# PowerManagementMysensors2.net
KiCad netlist of a schematic drawn in EAGLE
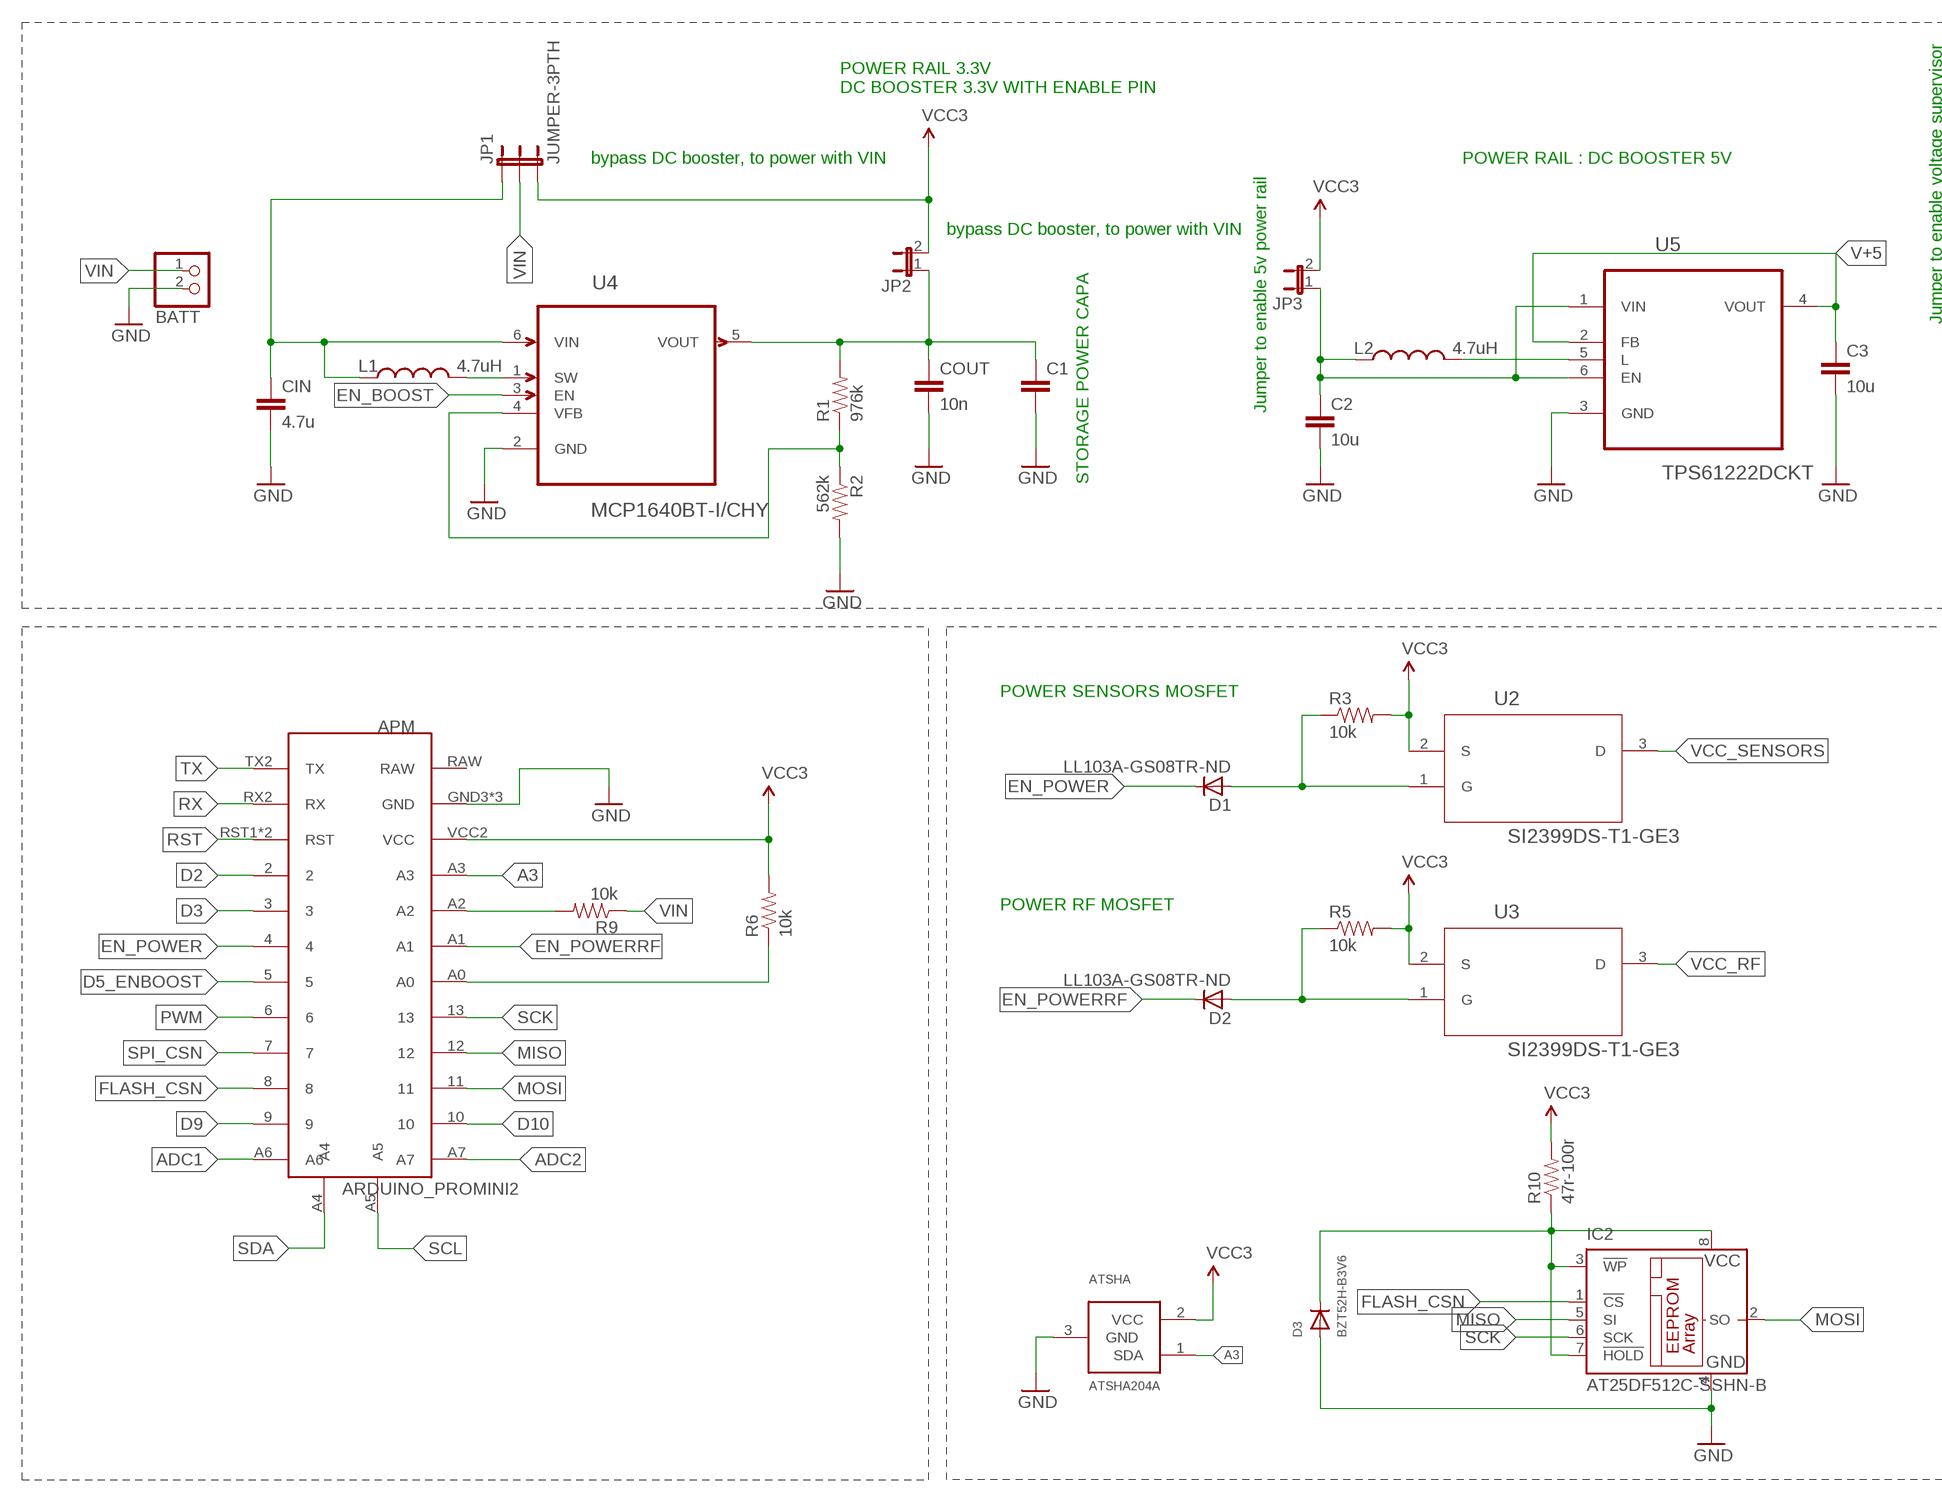
[diagram p0: schematic, sheet 1, part 1 of 2]
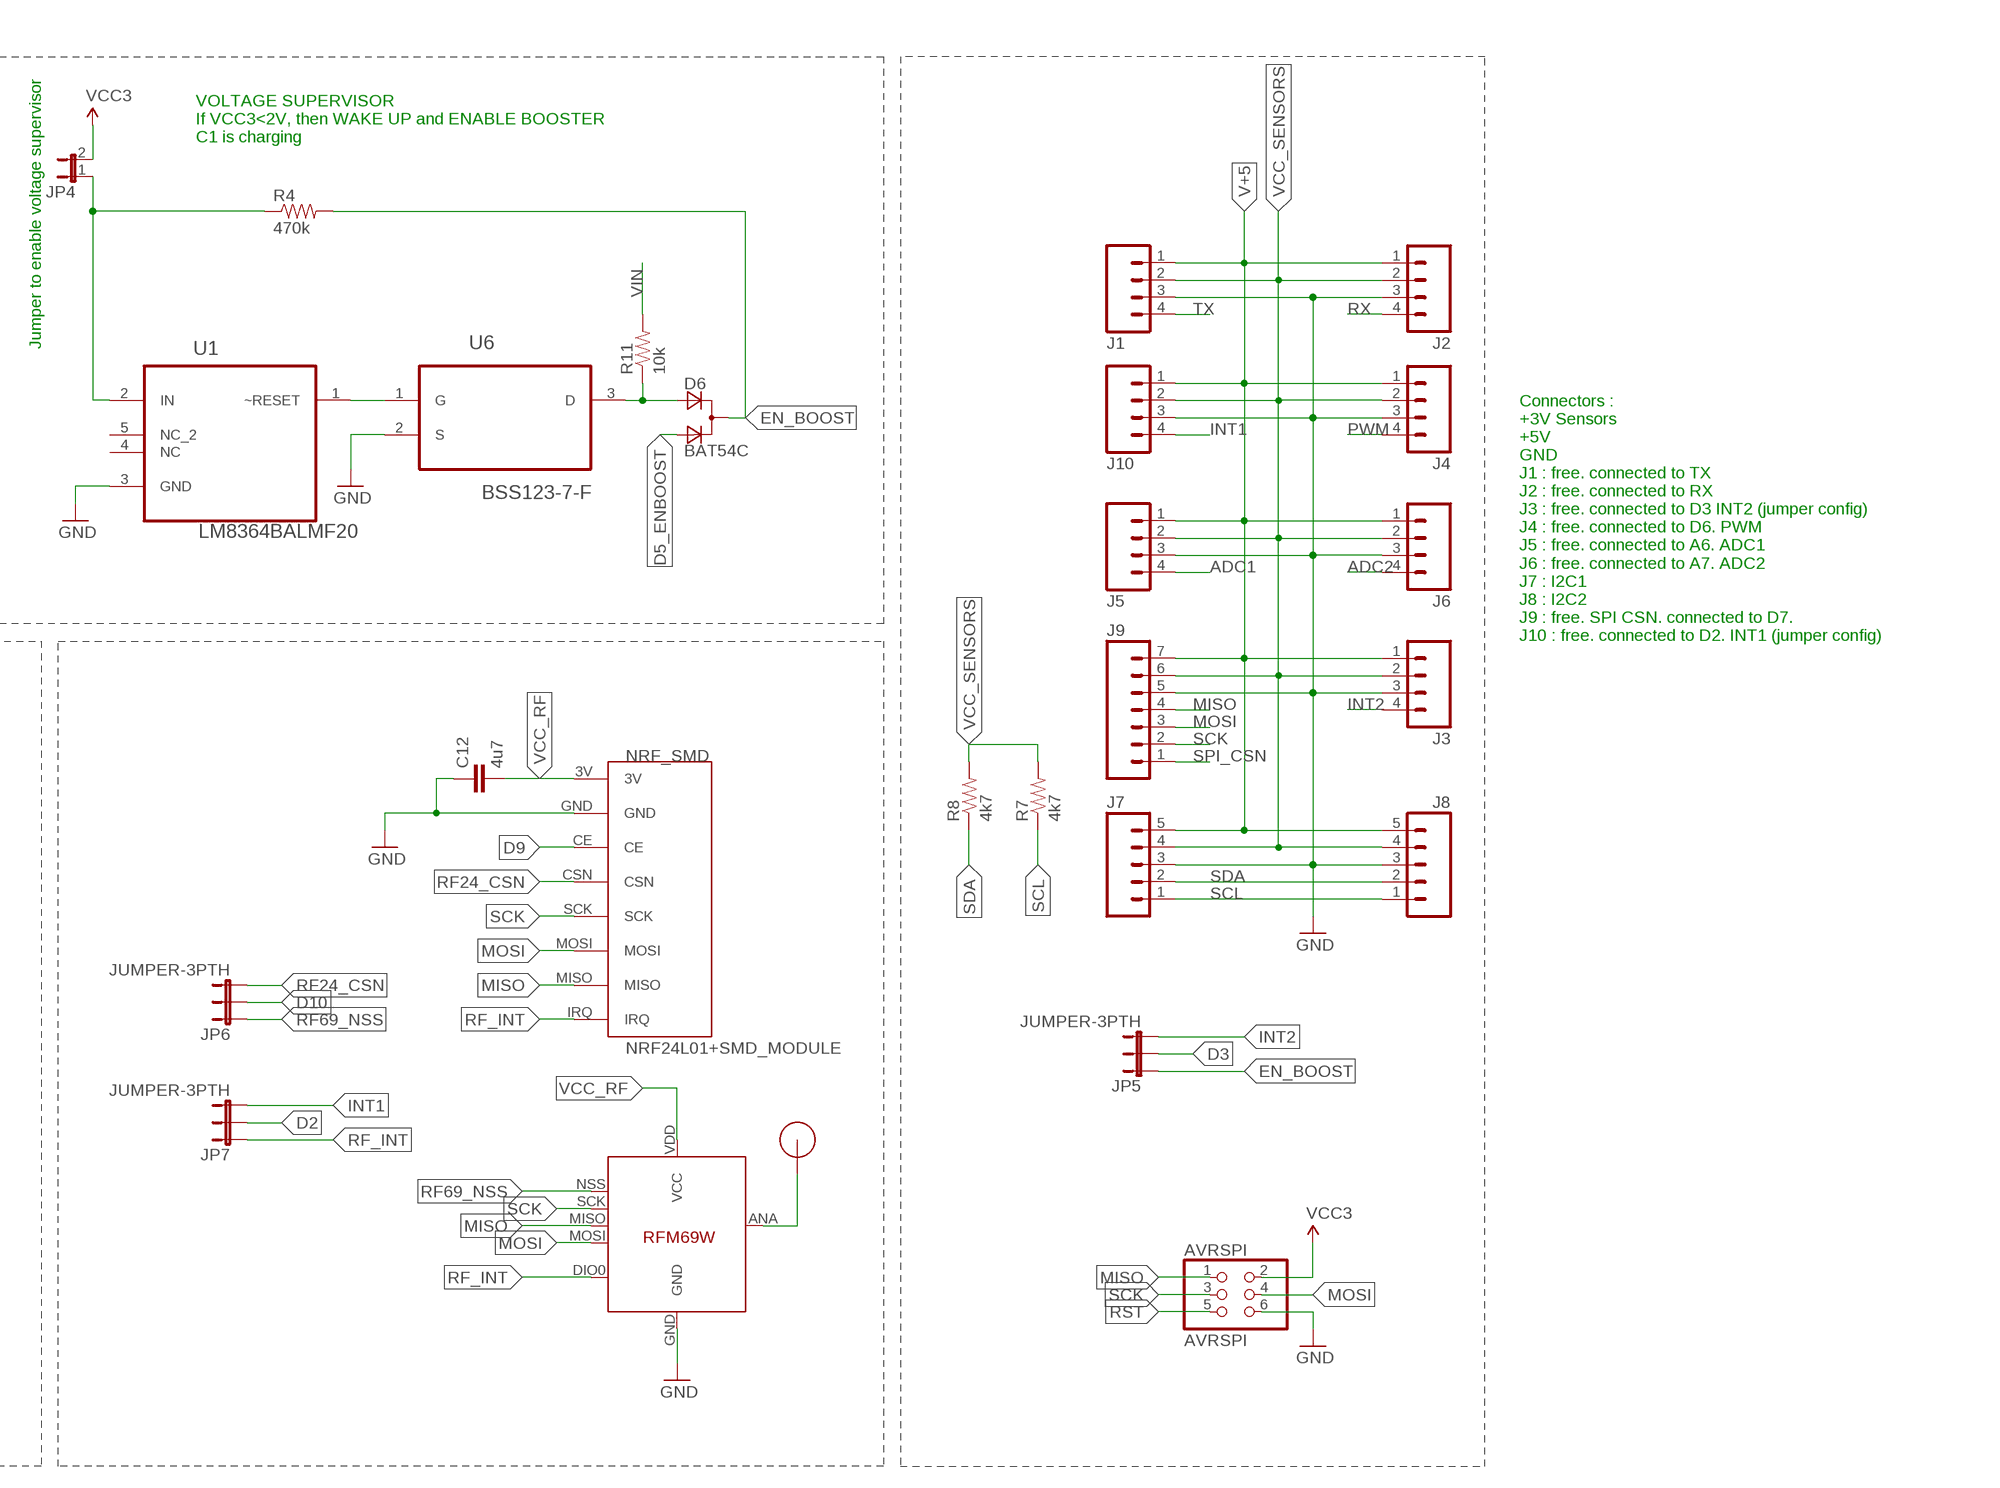
[diagram p1: schematic, sheet 1, part 2 of 2]

(export (version "E")
  (design (tool "Eeschema 10.0.6"))
  (components
    (comp (ref "ANT")
      (value "RFM12B_ANTENNA")
      (footprint "eagle-import:RFM12B-ANTENNA")
      (libsource (lib "eagle-import") (part "RFM12B_ANTENNA"))
    )
    (comp (ref "APM")
      (value "ARDUINO_PROMINI2")
      (footprint "eagle-import:ARDUINO_PROMINI2")
      (libsource (lib "eagle-import") (part "ARDUINO_PROMINI2"))
    )
    (comp (ref "ATSHA")
      (value "ATSHA204A")
      (footprint "eagle-import:SOT23")
      (libsource (lib "eagle-import") (part "ATSHA204A"))
    )
    (comp (ref "AVRSPI")
      (value "AVRSPI")
      (footprint "eagle-import:2X03")
      (libsource (lib "eagle-import") (part "PINHD-2X3"))
    )
    (comp (ref "BATT")
      (value "JST_2PIN-THM")
      (footprint "eagle-import:JST-PH-2-THM")
      (libsource (lib "eagle-import") (part "JST_2PIN-THM"))
    )
    (comp (ref "C1")
      (value "CAP1206")
      (footprint "eagle-import:1206")
      (libsource (lib "eagle-import") (part "SparkFun-Passives_CAP1206"))
    )
    (comp (ref "C2")
      (value "10u")
      (footprint "eagle-import:1206")
      (libsource (lib "eagle-import") (part "SparkFun-Passives_CAP1206"))
    )
    (comp (ref "C3")
      (value "10u")
      (footprint "eagle-import:1206")
      (libsource (lib "eagle-import") (part "SparkFun-Passives_CAP1206"))
    )
    (comp (ref "C12")
      (value "4u7")
      (footprint "eagle-import:1206")
      (libsource (lib "eagle-import") (part "CAP1206"))
    )
    (comp (ref "CIN")
      (value "4.7u")
      (footprint "eagle-import:1206")
      (libsource (lib "eagle-import") (part "SparkFun-Passives_CAP1206"))
    )
    (comp (ref "COUT")
      (value "10n")
      (footprint "eagle-import:1206")
      (libsource (lib "eagle-import") (part "SparkFun-Passives_CAP1206"))
    )
    (comp (ref "D1")
      (value "LL103A-GS08TR-ND")
      (footprint "eagle-import:SOD80")
      (libsource (lib "eagle-import") (part "D-SOD-80"))
    )
    (comp (ref "D2")
      (value "LL103A-GS08TR-ND")
      (footprint "eagle-import:SOD80")
      (libsource (lib "eagle-import") (part "D-SOD-80"))
    )
    (comp (ref "D3")
      (value "BZT52H-B3V6")
      (footprint "eagle-import:SOD-123")
      (libsource (lib "eagle-import") (part "DIODESOD-123"))
    )
    (comp (ref "D6")
      (value "BAT54C")
      (footprint "eagle-import:SOT-23")
      (libsource (lib "eagle-import") (part "D_2ASOT23"))
    )
    (comp (ref "IC2")
      (value "AT25DF512C-SSHN-B")
      (footprint "eagle-import:SO-08")
      (fields (field (name "MF") "MICROCHIP") (field (name "MPN") "25AA080/SN"))
      (libsource (lib "eagle-import") (part "25SNAA080"))
    )
    (comp (ref "J1")
      (value "M041X04_NO_SILK")
      (footprint "eagle-import:1X04_NO_SILK")
      (libsource (lib "eagle-import") (part "M041X04_NO_SILK"))
    )
    (comp (ref "J2")
      (value "M041X04_NO_SILK")
      (footprint "eagle-import:1X04_NO_SILK")
      (libsource (lib "eagle-import") (part "M041X04_NO_SILK"))
    )
    (comp (ref "J3")
      (value "M041X04_NO_SILK")
      (footprint "eagle-import:1X04_NO_SILK")
      (libsource (lib "eagle-import") (part "M041X04_NO_SILK"))
    )
    (comp (ref "J4")
      (value "M041X04_NO_SILK")
      (footprint "eagle-import:1X04_NO_SILK")
      (libsource (lib "eagle-import") (part "M041X04_NO_SILK"))
    )
    (comp (ref "J5")
      (value "M041X04_NO_SILK")
      (footprint "eagle-import:1X04_NO_SILK")
      (libsource (lib "eagle-import") (part "M041X04_NO_SILK"))
    )
    (comp (ref "J6")
      (value "M041X04_NO_SILK")
      (footprint "eagle-import:1X04_NO_SILK")
      (libsource (lib "eagle-import") (part "M041X04_NO_SILK"))
    )
    (comp (ref "J7")
      (value "M05NO_SILK")
      (footprint "eagle-import:1X05_NO_SILK")
      (libsource (lib "eagle-import") (part "M05NO_SILK"))
    )
    (comp (ref "J8")
      (value "M05NO_SILK")
      (footprint "eagle-import:1X05_NO_SILK")
      (libsource (lib "eagle-import") (part "M05NO_SILK"))
    )
    (comp (ref "J9")
      (value "M07")
      (footprint "eagle-import:1X07")
      (libsource (lib "eagle-import") (part "M07"))
    )
    (comp (ref "J10")
      (value "M041X04_NO_SILK")
      (footprint "eagle-import:1X04_NO_SILK")
      (libsource (lib "eagle-import") (part "M041X04_NO_SILK"))
    )
    (comp (ref "JP1")
      (value "JUMPER-3PTH")
      (footprint "eagle-import:1X03")
      (libsource (lib "eagle-import") (part "JUMPER-3PTH"))
    )
    (comp (ref "JP2")
      (value "JUMPER-2PTH")
      (footprint "eagle-import:1X02")
      (libsource (lib "eagle-import") (part "JUMPER-2PTH"))
    )
    (comp (ref "JP3")
      (value "JUMPER-2PTH")
      (footprint "eagle-import:1X02")
      (libsource (lib "eagle-import") (part "JUMPER-2PTH"))
    )
    (comp (ref "JP4")
      (value "JUMPER-2PTH")
      (footprint "eagle-import:1X02")
      (libsource (lib "eagle-import") (part "JUMPER-2PTH"))
    )
    (comp (ref "JP5")
      (value "JUMPER-3PTH")
      (footprint "eagle-import:1X03")
      (libsource (lib "eagle-import") (part "JUMPER-3PTH"))
    )
    (comp (ref "JP6")
      (value "JUMPER-3PTH")
      (footprint "eagle-import:1X03")
      (libsource (lib "eagle-import") (part "JUMPER-3PTH"))
    )
    (comp (ref "JP7")
      (value "JUMPER-3PTH")
      (footprint "eagle-import:1X03")
      (libsource (lib "eagle-import") (part "JUMPER-3PTH"))
    )
    (comp (ref "L1")
      (value "4.7uH")
      (footprint "eagle-import:0805")
      (libsource (lib "eagle-import") (part "INDUCTOR0805"))
    )
    (comp (ref "L2")
      (value "4.7uH")
      (footprint "eagle-import:0805")
      (libsource (lib "eagle-import") (part "INDUCTOR0805"))
    )
    (comp (ref "NRF_SMD")
      (value "NRF24L01+SMD_MODULE")
      (footprint "eagle-import:NRF24L01+SMD_MODULE")
      (libsource (lib "eagle-import") (part "NRF24L01+SMD_MODULE"))
    )
    (comp (ref "R1")
      (value "976k")
      (footprint "eagle-import:1206")
      (libsource (lib "eagle-import") (part "RESISTOR1206"))
    )
    (comp (ref "R2")
      (value "562k")
      (footprint "eagle-import:1206")
      (libsource (lib "eagle-import") (part "RESISTOR1206"))
    )
    (comp (ref "R3")
      (value "10k")
      (footprint "eagle-import:1206")
      (libsource (lib "eagle-import") (part "RESISTOR1206"))
    )
    (comp (ref "R4")
      (value "470k")
      (footprint "eagle-import:1206")
      (libsource (lib "eagle-import") (part "RESISTOR1206"))
    )
    (comp (ref "R5")
      (value "10k")
      (footprint "eagle-import:1206")
      (libsource (lib "eagle-import") (part "RESISTOR1206"))
    )
    (comp (ref "R6")
      (value "10k")
      (footprint "eagle-import:1206")
      (libsource (lib "eagle-import") (part "RESISTOR1206"))
    )
    (comp (ref "R7")
      (value "4k7")
      (footprint "eagle-import:1206")
      (libsource (lib "eagle-import") (part "RESISTOR1206"))
    )
    (comp (ref "R8")
      (value "4k7")
      (footprint "eagle-import:1206")
      (libsource (lib "eagle-import") (part "RESISTOR1206"))
    )
    (comp (ref "R9")
      (value "10k")
      (footprint "eagle-import:1206")
      (libsource (lib "eagle-import") (part "RESISTOR1206"))
    )
    (comp (ref "R10")
      (value "47r-100r")
      (footprint "eagle-import:1206")
      (libsource (lib "eagle-import") (part "RESISTOR1206"))
    )
    (comp (ref "R11")
      (value "10k")
      (footprint "eagle-import:1206")
      (libsource (lib "eagle-import") (part "RESISTOR1206"))
    )
    (comp (ref "RFM69")
      (value "RFM69")
      (footprint "eagle-import:RFM69W-MINPADS")
      (libsource (lib "eagle-import") (part "RFM69"))
    )
    (comp (ref "U1")
      (value "LM8364BALMF20")
      (footprint "eagle-import:SOT95P284X122-5N")
      (libsource (lib "eagle-import") (part "LM8364BALMF20"))
    )
    (comp (ref "U2")
      (value "SI2399DS-T1-GE3")
      (footprint "eagle-import:SOT95P237X112-3N")
      (libsource (lib "eagle-import") (part "SI2399DS-T1-GE3"))
    )
    (comp (ref "U3")
      (value "SI2399DS-T1-GE3")
      (footprint "eagle-import:SOT95P237X112-3N")
      (libsource (lib "eagle-import") (part "SI2399DS-T1-GE3"))
    )
    (comp (ref "U4")
      (value "MCP1640BT-I/CHY")
      (footprint "eagle-import:SOT95P270X145-6N")
      (libsource (lib "eagle-import") (part "MCP1640BT-I/CHY"))
    )
    (comp (ref "U5")
      (value "TPS61222DCKT")
      (footprint "eagle-import:SOT65P210X110-6N")
      (libsource (lib "eagle-import") (part "TPS61222DCKT"))
    )
    (comp (ref "U6")
      (value "BSS123-7-F")
      (footprint "eagle-import:SOT95P240X110-3N")
      (libsource (lib "eagle-import") (part "BSS123-7-F"))
    )
  )
  (nets
    (net (code "1") (name "A3") (class "Default")
      (node (ref "APM") (pin "A3") (pinfunction "A3_A3") (pintype "bidirectional"))
      (node (ref "ATSHA") (pin "1") (pinfunction "SDA_1") (pintype "bidirectional"))
    )
    (net (code "2") (name "ADC1") (class "Default")
      (node (ref "APM") (pin "A6") (pinfunction "A6_A6") (pintype "bidirectional"))
      (node (ref "J5") (pin "4") (pinfunction "4_4") (pintype "passive"))
    )
    (net (code "3") (name "ADC2") (class "Default")
      (node (ref "APM") (pin "A7") (pinfunction "A7_A7") (pintype "bidirectional"))
      (node (ref "J6") (pin "4") (pinfunction "4_4") (pintype "passive"))
    )
    (net (code "4") (name "D2") (class "Default")
      (node (ref "APM") (pin "2") (pinfunction "2_2") (pintype "bidirectional"))
      (node (ref "JP7") (pin "2") (pinfunction "2_2") (pintype "passive"))
    )
    (net (code "5") (name "D3") (class "Default")
      (node (ref "APM") (pin "3") (pinfunction "3_3") (pintype "bidirectional"))
      (node (ref "JP5") (pin "2") (pinfunction "2_2") (pintype "passive"))
    )
    (net (code "6") (name "D5_ENBOOST") (class "Default")
      (node (ref "APM") (pin "5") (pinfunction "5_5") (pintype "bidirectional"))
      (node (ref "D6") (pin "3") (pinfunction "A2_3") (pintype "passive"))
    )
    (net (code "7") (name "D9") (class "Default")
      (node (ref "APM") (pin "9") (pinfunction "9_9") (pintype "bidirectional"))
      (node (ref "NRF_SMD") (pin "CE") (pinfunction "CE_CE") (pintype "bidirectional"))
    )
    (net (code "8") (name "D10") (class "Default")
      (node (ref "APM") (pin "10") (pinfunction "10_10") (pintype "bidirectional"))
      (node (ref "JP6") (pin "2") (pinfunction "2_2") (pintype "passive"))
    )
    (net (code "9") (name "EN_BOOST") (class "Default")
      (node (ref "D6") (pin "1") (pinfunction "C_1") (pintype "passive"))
      (node (ref "JP5") (pin "1") (pinfunction "1_1") (pintype "passive"))
      (node (ref "R4") (pin "2") (pinfunction "2_2") (pintype "passive"))
      (node (ref "U4") (pin "3") (pinfunction "EN_3") (pintype "input"))
    )
    (net (code "10") (name "EN_POWER") (class "Default")
      (node (ref "APM") (pin "4") (pinfunction "4_4") (pintype "bidirectional"))
      (node (ref "D1") (pin "1") (pinfunction "C_1") (pintype "passive"))
    )
    (net (code "11") (name "EN_POWERRF") (class "Default")
      (node (ref "APM") (pin "A1") (pinfunction "A1_A1") (pintype "bidirectional"))
      (node (ref "D2") (pin "1") (pinfunction "C_1") (pintype "passive"))
    )
    (net (code "12") (name "FLASH_CSN") (class "Default")
      (node (ref "APM") (pin "8") (pinfunction "8_8") (pintype "bidirectional"))
      (node (ref "IC2") (pin "1") (pinfunction "~{CS}_1") (pintype "input"))
    )
    (net (code "13") (name "GND") (class "Default")
      (node (ref "APM") (pin "GND3") (pinfunction "GND_GND3") (pintype "bidirectional"))
      (node (ref "APM") (pin "GND4") (pinfunction "GND_GND4") (pintype "bidirectional"))
      (node (ref "APM") (pin "GND5") (pinfunction "GND_GND5") (pintype "bidirectional"))
      (node (ref "ATSHA") (pin "3") (pinfunction "GND_3") (pintype "bidirectional"))
      (node (ref "AVRSPI") (pin "6") (pinfunction "6_6") (pintype "passive"))
      (node (ref "BATT") (pin "2") (pinfunction "1_2") (pintype "passive"))
      (node (ref "C1") (pin "2") (pinfunction "2_2") (pintype "passive"))
      (node (ref "C12") (pin "1") (pinfunction "1_1") (pintype "passive"))
      (node (ref "C2") (pin "2") (pinfunction "2_2") (pintype "passive"))
      (node (ref "C3") (pin "2") (pinfunction "2_2") (pintype "passive"))
      (node (ref "CIN") (pin "2") (pinfunction "2_2") (pintype "passive"))
      (node (ref "COUT") (pin "2") (pinfunction "2_2") (pintype "passive"))
      (node (ref "D3") (pin "A") (pinfunction "A_A") (pintype "passive"))
      (node (ref "IC2") (pin "4") (pinfunction "GND_4") (pintype "power_in"))
      (node (ref "J1") (pin "3") (pinfunction "3_3") (pintype "passive"))
      (node (ref "J10") (pin "3") (pinfunction "3_3") (pintype "passive"))
      (node (ref "J2") (pin "3") (pinfunction "3_3") (pintype "passive"))
      (node (ref "J3") (pin "3") (pinfunction "3_3") (pintype "passive"))
      (node (ref "J4") (pin "3") (pinfunction "3_3") (pintype "passive"))
      (node (ref "J5") (pin "3") (pinfunction "3_3") (pintype "passive"))
      (node (ref "J6") (pin "3") (pinfunction "3_3") (pintype "passive"))
      (node (ref "J7") (pin "3") (pinfunction "3_3") (pintype "passive"))
      (node (ref "J8") (pin "3") (pinfunction "3_3") (pintype "passive"))
      (node (ref "J9") (pin "5") (pinfunction "5_5") (pintype "passive"))
      (node (ref "NRF_SMD") (pin "GND") (pinfunction "GND_GND") (pintype "bidirectional"))
      (node (ref "R2") (pin "2") (pinfunction "2_2") (pintype "passive"))
      (node (ref "RFM69") (pin "GND") (pinfunction "GND_GND") (pintype "power_in"))
      (node (ref "U1") (pin "3") (pinfunction "GND_3") (pintype "passive"))
      (node (ref "U4") (pin "2") (pinfunction "GND_2") (pintype "passive"))
      (node (ref "U5") (pin "3") (pinfunction "GND_3") (pintype "passive"))
      (node (ref "U6") (pin "2") (pinfunction "S_2") (pintype "passive"))
    )
    (net (code "14") (name "INT1") (class "Default")
      (node (ref "J10") (pin "4") (pinfunction "4_4") (pintype "passive"))
      (node (ref "JP7") (pin "3") (pinfunction "3_3") (pintype "passive"))
    )
    (net (code "15") (name "INT2") (class "Default")
      (node (ref "J3") (pin "4") (pinfunction "4_4") (pintype "passive"))
      (node (ref "JP5") (pin "3") (pinfunction "3_3") (pintype "passive"))
    )
    (net (code "16") (name "MISO") (class "Default")
      (node (ref "APM") (pin "12") (pinfunction "12_12") (pintype "bidirectional"))
      (node (ref "AVRSPI") (pin "1") (pinfunction "1_1") (pintype "passive"))
      (node (ref "IC2") (pin "5") (pinfunction "SI_5") (pintype "input"))
      (node (ref "J9") (pin "4") (pinfunction "4_4") (pintype "passive"))
      (node (ref "NRF_SMD") (pin "MISO") (pinfunction "MISO_MISO") (pintype "bidirectional"))
      (node (ref "RFM69") (pin "MISO") (pinfunction "MISO_MISO") (pintype "input"))
    )
    (net (code "17") (name "MOSI") (class "Default")
      (node (ref "APM") (pin "11") (pinfunction "11_11") (pintype "bidirectional"))
      (node (ref "AVRSPI") (pin "4") (pinfunction "4_4") (pintype "passive"))
      (node (ref "IC2") (pin "2") (pinfunction "SO_2") (pintype "bidirectional"))
      (node (ref "J9") (pin "3") (pinfunction "3_3") (pintype "passive"))
      (node (ref "NRF_SMD") (pin "MOSI") (pinfunction "MOSI_MOSI") (pintype "bidirectional"))
      (node (ref "RFM69") (pin "MOSI") (pinfunction "MOSI_MOSI") (pintype "output"))
    )
    (net (code "18") (name "Net-(ANT-1)") (class "Default")
      (node (ref "ANT") (pin "P$1") (pinfunction "1_P$1") (pintype "bidirectional"))
      (node (ref "RFM69") (pin "ANA") (pinfunction "ANT_ANA") (pintype "passive"))
    )
    (net (code "19") (name "Net-(APM-PadA0)") (class "Default")
      (node (ref "APM") (pin "A0") (pinfunction "A0_A0") (pintype "bidirectional"))
      (node (ref "R6") (pin "1") (pinfunction "1_1") (pintype "passive"))
    )
    (net (code "20") (name "Net-(APM-PadA2)") (class "Default")
      (node (ref "APM") (pin "A2") (pinfunction "A2_A2") (pintype "bidirectional"))
      (node (ref "R9") (pin "2") (pinfunction "2_2") (pintype "passive"))
    )
    (net (code "21") (name "Net-(D1-A)") (class "Default")
      (node (ref "D1") (pin "2") (pinfunction "A_2") (pintype "passive"))
      (node (ref "R3") (pin "1") (pinfunction "1_1") (pintype "passive"))
      (node (ref "U2") (pin "1") (pinfunction "G_1") (pintype "passive"))
    )
    (net (code "22") (name "Net-(D2-A)") (class "Default")
      (node (ref "D2") (pin "2") (pinfunction "A_2") (pintype "passive"))
      (node (ref "R5") (pin "1") (pinfunction "1_1") (pintype "passive"))
      (node (ref "U3") (pin "1") (pinfunction "G_1") (pintype "passive"))
    )
    (net (code "23") (name "Net-(D6-A1)") (class "Default")
      (node (ref "D6") (pin "2") (pinfunction "A1_2") (pintype "passive"))
      (node (ref "R11") (pin "1") (pinfunction "1_1") (pintype "passive"))
      (node (ref "U6") (pin "3") (pinfunction "D_3") (pintype "passive"))
    )
    (net (code "24") (name "Net-(IC2-VCC)") (class "Default")
      (node (ref "D3") (pin "C") (pinfunction "C_C") (pintype "passive"))
      (node (ref "IC2") (pin "3") (pinfunction "~{WP}_3") (pintype "input"))
      (node (ref "IC2") (pin "7") (pinfunction "~{HOLD}_7") (pintype "input"))
      (node (ref "IC2") (pin "8") (pinfunction "VCC_8") (pintype "power_in"))
      (node (ref "R10") (pin "1") (pinfunction "1_1") (pintype "passive"))
    )
    (net (code "25") (name "Net-(U1-IN)") (class "Default")
      (node (ref "JP4") (pin "1") (pinfunction "1_1") (pintype "passive"))
      (node (ref "R4") (pin "1") (pinfunction "1_1") (pintype "passive"))
      (node (ref "U1") (pin "2") (pinfunction "IN_2") (pintype "input"))
    )
    (net (code "26") (name "Net-(U1-~{RESET})") (class "Default")
      (node (ref "U1") (pin "1") (pinfunction "~{RESET}_1") (pintype "output"))
      (node (ref "U6") (pin "1") (pinfunction "G_1") (pintype "passive"))
    )
    (net (code "27") (name "Net-(U4-SW)") (class "Default")
      (node (ref "L1") (pin "2") (pinfunction "2_2") (pintype "passive"))
      (node (ref "U4") (pin "1") (pinfunction "SW_1") (pintype "input"))
    )
    (net (code "28") (name "Net-(U4-VFB)") (class "Default")
      (node (ref "R1") (pin "1") (pinfunction "1_1") (pintype "passive"))
      (node (ref "R2") (pin "1") (pinfunction "1_1") (pintype "passive"))
      (node (ref "U4") (pin "4") (pinfunction "VFB_4") (pintype "input"))
    )
    (net (code "29") (name "Net-(U4-VIN)") (class "Default")
      (node (ref "CIN") (pin "1") (pinfunction "1_1") (pintype "passive"))
      (node (ref "JP1") (pin "1") (pinfunction "1_1") (pintype "passive"))
      (node (ref "L1") (pin "1") (pinfunction "1_1") (pintype "passive"))
      (node (ref "U4") (pin "6") (pinfunction "VIN_6") (pintype "input"))
    )
    (net (code "30") (name "Net-(U4-VOUT)") (class "Default")
      (node (ref "C1") (pin "1") (pinfunction "1_1") (pintype "passive"))
      (node (ref "COUT") (pin "1") (pinfunction "1_1") (pintype "passive"))
      (node (ref "JP2") (pin "1") (pinfunction "1_1") (pintype "passive"))
      (node (ref "R1") (pin "2") (pinfunction "2_2") (pintype "passive"))
      (node (ref "U4") (pin "5") (pinfunction "VOUT_5") (pintype "output"))
    )
    (net (code "31") (name "Net-(U5-EN)") (class "Default")
      (node (ref "C2") (pin "1") (pinfunction "1_1") (pintype "passive"))
      (node (ref "JP3") (pin "1") (pinfunction "1_1") (pintype "passive"))
      (node (ref "L2") (pin "1") (pinfunction "1_1") (pintype "passive"))
      (node (ref "U5") (pin "1") (pinfunction "VIN_1") (pintype "input"))
      (node (ref "U5") (pin "6") (pinfunction "EN_6") (pintype "input"))
    )
    (net (code "32") (name "Net-(U5-L)") (class "Default")
      (node (ref "L2") (pin "2") (pinfunction "2_2") (pintype "passive"))
      (node (ref "U5") (pin "5") (pinfunction "L_5") (pintype "passive"))
    )
    (net (code "33") (name "PWM") (class "Default")
      (node (ref "APM") (pin "6") (pinfunction "6_6") (pintype "bidirectional"))
      (node (ref "J4") (pin "4") (pinfunction "4_4") (pintype "passive"))
    )
    (net (code "34") (name "RF24_CSN") (class "Default")
      (node (ref "JP6") (pin "3") (pinfunction "3_3") (pintype "passive"))
      (node (ref "NRF_SMD") (pin "CSN") (pinfunction "CSN_CSN") (pintype "bidirectional"))
    )
    (net (code "35") (name "RF69_NSS") (class "Default")
      (node (ref "JP6") (pin "1") (pinfunction "1_1") (pintype "passive"))
      (node (ref "RFM69") (pin "NSS") (pinfunction "SEL_NSS") (pintype "input"))
    )
    (net (code "36") (name "RF_INT") (class "Default")
      (node (ref "JP7") (pin "1") (pinfunction "1_1") (pintype "passive"))
      (node (ref "NRF_SMD") (pin "IRQ") (pinfunction "IRQ_IRQ") (pintype "bidirectional"))
      (node (ref "RFM69") (pin "DIO0") (pinfunction "DIO0_DIO0") (pintype "open_collector"))
    )
    (net (code "37") (name "RST") (class "Default")
      (node (ref "APM") (pin "RST1") (pinfunction "RST_RST1") (pintype "bidirectional"))
      (node (ref "APM") (pin "RST2") (pinfunction "RST_RST2") (pintype "bidirectional"))
      (node (ref "AVRSPI") (pin "5") (pinfunction "5_5") (pintype "passive"))
    )
    (net (code "38") (name "RX") (class "Default")
      (node (ref "APM") (pin "RX2") (pinfunction "RX_RX2") (pintype "bidirectional"))
      (node (ref "J2") (pin "4") (pinfunction "4_4") (pintype "passive"))
    )
    (net (code "39") (name "SCK") (class "Default")
      (node (ref "APM") (pin "13") (pinfunction "13_13") (pintype "bidirectional"))
      (node (ref "AVRSPI") (pin "3") (pinfunction "3_3") (pintype "passive"))
      (node (ref "IC2") (pin "6") (pinfunction "SCK_6") (pintype "input"))
      (node (ref "J9") (pin "2") (pinfunction "2_2") (pintype "passive"))
      (node (ref "NRF_SMD") (pin "SCK") (pinfunction "SCK_SCK") (pintype "bidirectional"))
      (node (ref "RFM69") (pin "SCK") (pinfunction "SCK_SCK") (pintype "input"))
    )
    (net (code "40") (name "SCL") (class "Default")
      (node (ref "APM") (pin "A5") (pinfunction "A5_A5") (pintype "bidirectional"))
      (node (ref "J7") (pin "1") (pinfunction "1_1") (pintype "passive"))
      (node (ref "J8") (pin "1") (pinfunction "1_1") (pintype "passive"))
      (node (ref "R7") (pin "1") (pinfunction "1_1") (pintype "passive"))
    )
    (net (code "41") (name "SDA") (class "Default")
      (node (ref "APM") (pin "A4") (pinfunction "A4_A4") (pintype "bidirectional"))
      (node (ref "J7") (pin "2") (pinfunction "2_2") (pintype "passive"))
      (node (ref "J8") (pin "2") (pinfunction "2_2") (pintype "passive"))
      (node (ref "R8") (pin "1") (pinfunction "1_1") (pintype "passive"))
    )
    (net (code "42") (name "SPI_CSN") (class "Default")
      (node (ref "APM") (pin "7") (pinfunction "7_7") (pintype "bidirectional"))
      (node (ref "J9") (pin "1") (pinfunction "1_1") (pintype "passive"))
    )
    (net (code "43") (name "TX") (class "Default")
      (node (ref "APM") (pin "TX2") (pinfunction "TX_TX2") (pintype "bidirectional"))
      (node (ref "J1") (pin "4") (pinfunction "4_4") (pintype "passive"))
    )
    (net (code "44") (name "V+5") (class "Default")
      (node (ref "C3") (pin "1") (pinfunction "1_1") (pintype "passive"))
      (node (ref "J1") (pin "1") (pinfunction "1_1") (pintype "passive"))
      (node (ref "J10") (pin "1") (pinfunction "1_1") (pintype "passive"))
      (node (ref "J2") (pin "1") (pinfunction "1_1") (pintype "passive"))
      (node (ref "J3") (pin "1") (pinfunction "1_1") (pintype "passive"))
      (node (ref "J4") (pin "1") (pinfunction "1_1") (pintype "passive"))
      (node (ref "J5") (pin "1") (pinfunction "1_1") (pintype "passive"))
      (node (ref "J6") (pin "1") (pinfunction "1_1") (pintype "passive"))
      (node (ref "J7") (pin "5") (pinfunction "5_5") (pintype "passive"))
      (node (ref "J8") (pin "5") (pinfunction "5_5") (pintype "passive"))
      (node (ref "J9") (pin "7") (pinfunction "7_7") (pintype "passive"))
      (node (ref "U5") (pin "2") (pinfunction "FB_2") (pintype "input"))
      (node (ref "U5") (pin "4") (pinfunction "VOUT_4") (pintype "output"))
    )
    (net (code "45") (name "VCC3") (class "Default")
      (node (ref "APM") (pin "VCC2") (pinfunction "VCC_VCC2") (pintype "bidirectional"))
      (node (ref "ATSHA") (pin "2") (pinfunction "VCC_2") (pintype "bidirectional"))
      (node (ref "AVRSPI") (pin "2") (pinfunction "2_2") (pintype "passive"))
      (node (ref "JP1") (pin "3") (pinfunction "3_3") (pintype "passive"))
      (node (ref "JP2") (pin "2") (pinfunction "2_2") (pintype "passive"))
      (node (ref "JP3") (pin "2") (pinfunction "2_2") (pintype "passive"))
      (node (ref "JP4") (pin "2") (pinfunction "2_2") (pintype "passive"))
      (node (ref "R10") (pin "2") (pinfunction "2_2") (pintype "passive"))
      (node (ref "R3") (pin "2") (pinfunction "2_2") (pintype "passive"))
      (node (ref "R5") (pin "2") (pinfunction "2_2") (pintype "passive"))
      (node (ref "R6") (pin "2") (pinfunction "2_2") (pintype "passive"))
      (node (ref "U2") (pin "2") (pinfunction "S_2") (pintype "passive"))
      (node (ref "U3") (pin "2") (pinfunction "S_2") (pintype "passive"))
    )
    (net (code "46") (name "VCC_RF") (class "Default")
      (node (ref "C12") (pin "2") (pinfunction "2_2") (pintype "passive"))
      (node (ref "NRF_SMD") (pin "3V") (pinfunction "3V_3V") (pintype "bidirectional"))
      (node (ref "RFM69") (pin "VDD") (pinfunction "VCC_VDD") (pintype "power_in"))
      (node (ref "U3") (pin "3") (pinfunction "D_3") (pintype "passive"))
    )
    (net (code "47") (name "VCC_SENSORS") (class "Default")
      (node (ref "J1") (pin "2") (pinfunction "2_2") (pintype "passive"))
      (node (ref "J10") (pin "2") (pinfunction "2_2") (pintype "passive"))
      (node (ref "J2") (pin "2") (pinfunction "2_2") (pintype "passive"))
      (node (ref "J3") (pin "2") (pinfunction "2_2") (pintype "passive"))
      (node (ref "J4") (pin "2") (pinfunction "2_2") (pintype "passive"))
      (node (ref "J5") (pin "2") (pinfunction "2_2") (pintype "passive"))
      (node (ref "J6") (pin "2") (pinfunction "2_2") (pintype "passive"))
      (node (ref "J7") (pin "4") (pinfunction "4_4") (pintype "passive"))
      (node (ref "J8") (pin "4") (pinfunction "4_4") (pintype "passive"))
      (node (ref "J9") (pin "6") (pinfunction "6_6") (pintype "passive"))
      (node (ref "R7") (pin "2") (pinfunction "2_2") (pintype "passive"))
      (node (ref "R8") (pin "2") (pinfunction "2_2") (pintype "passive"))
      (node (ref "U2") (pin "3") (pinfunction "D_3") (pintype "passive"))
    )
    (net (code "48") (name "VIN") (class "Default")
      (node (ref "BATT") (pin "1") (pinfunction "2_1") (pintype "passive"))
      (node (ref "JP1") (pin "2") (pinfunction "2_2") (pintype "passive"))
      (node (ref "R11") (pin "2") (pinfunction "2_2") (pintype "passive"))
      (node (ref "R9") (pin "1") (pinfunction "1_1") (pintype "passive"))
    )
    (net (code "49") (name "unconnected-(APM-PadRAW)") (class "Default")
      (node (ref "APM") (pin "RAW") (pinfunction "RAW_RAW") (pintype "bidirectional"))
    )
    (net (code "50") (name "unconnected-(U1-NC-Pad4)") (class "Default")
      (node (ref "U1") (pin "4") (pinfunction "NC_4") (pintype "no_connect"))
    )
    (net (code "51") (name "unconnected-(U1-NC_2-Pad5)") (class "Default")
      (node (ref "U1") (pin "5") (pinfunction "NC_2_5") (pintype "no_connect"))
    )
  )
)
